# Project_OLIA.net
KiCad netlist of a schematic drawn in Altium Designer
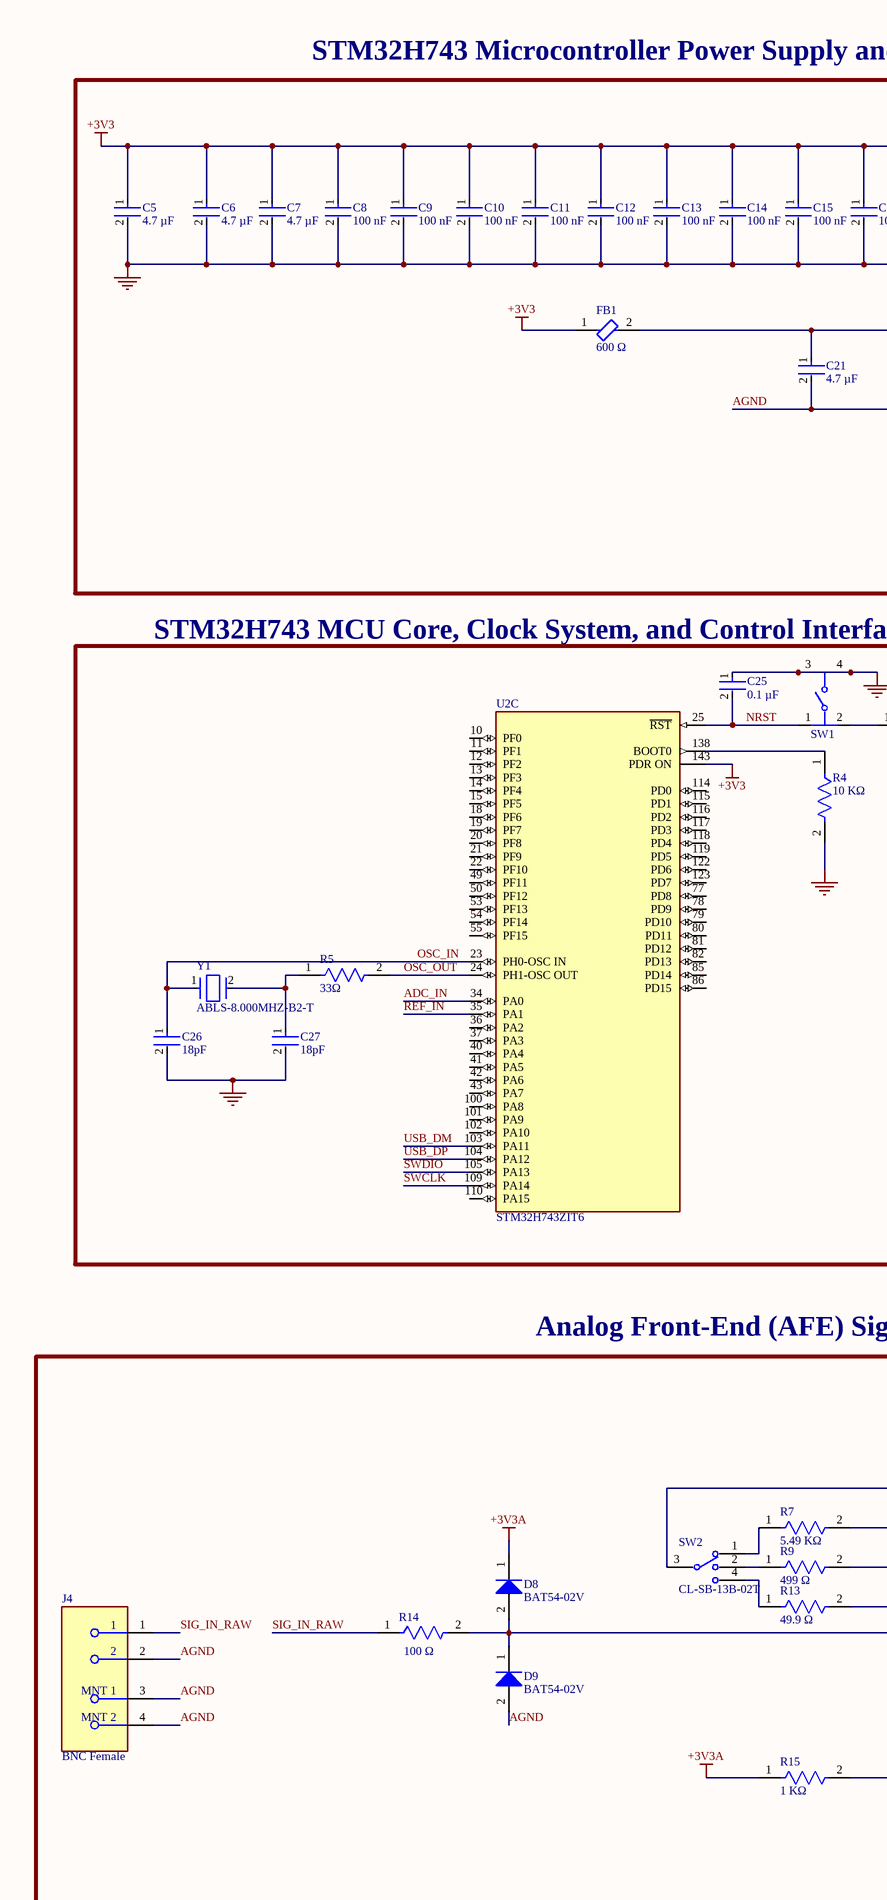
[diagram p0: Project_OLIA.SchDoc, left]
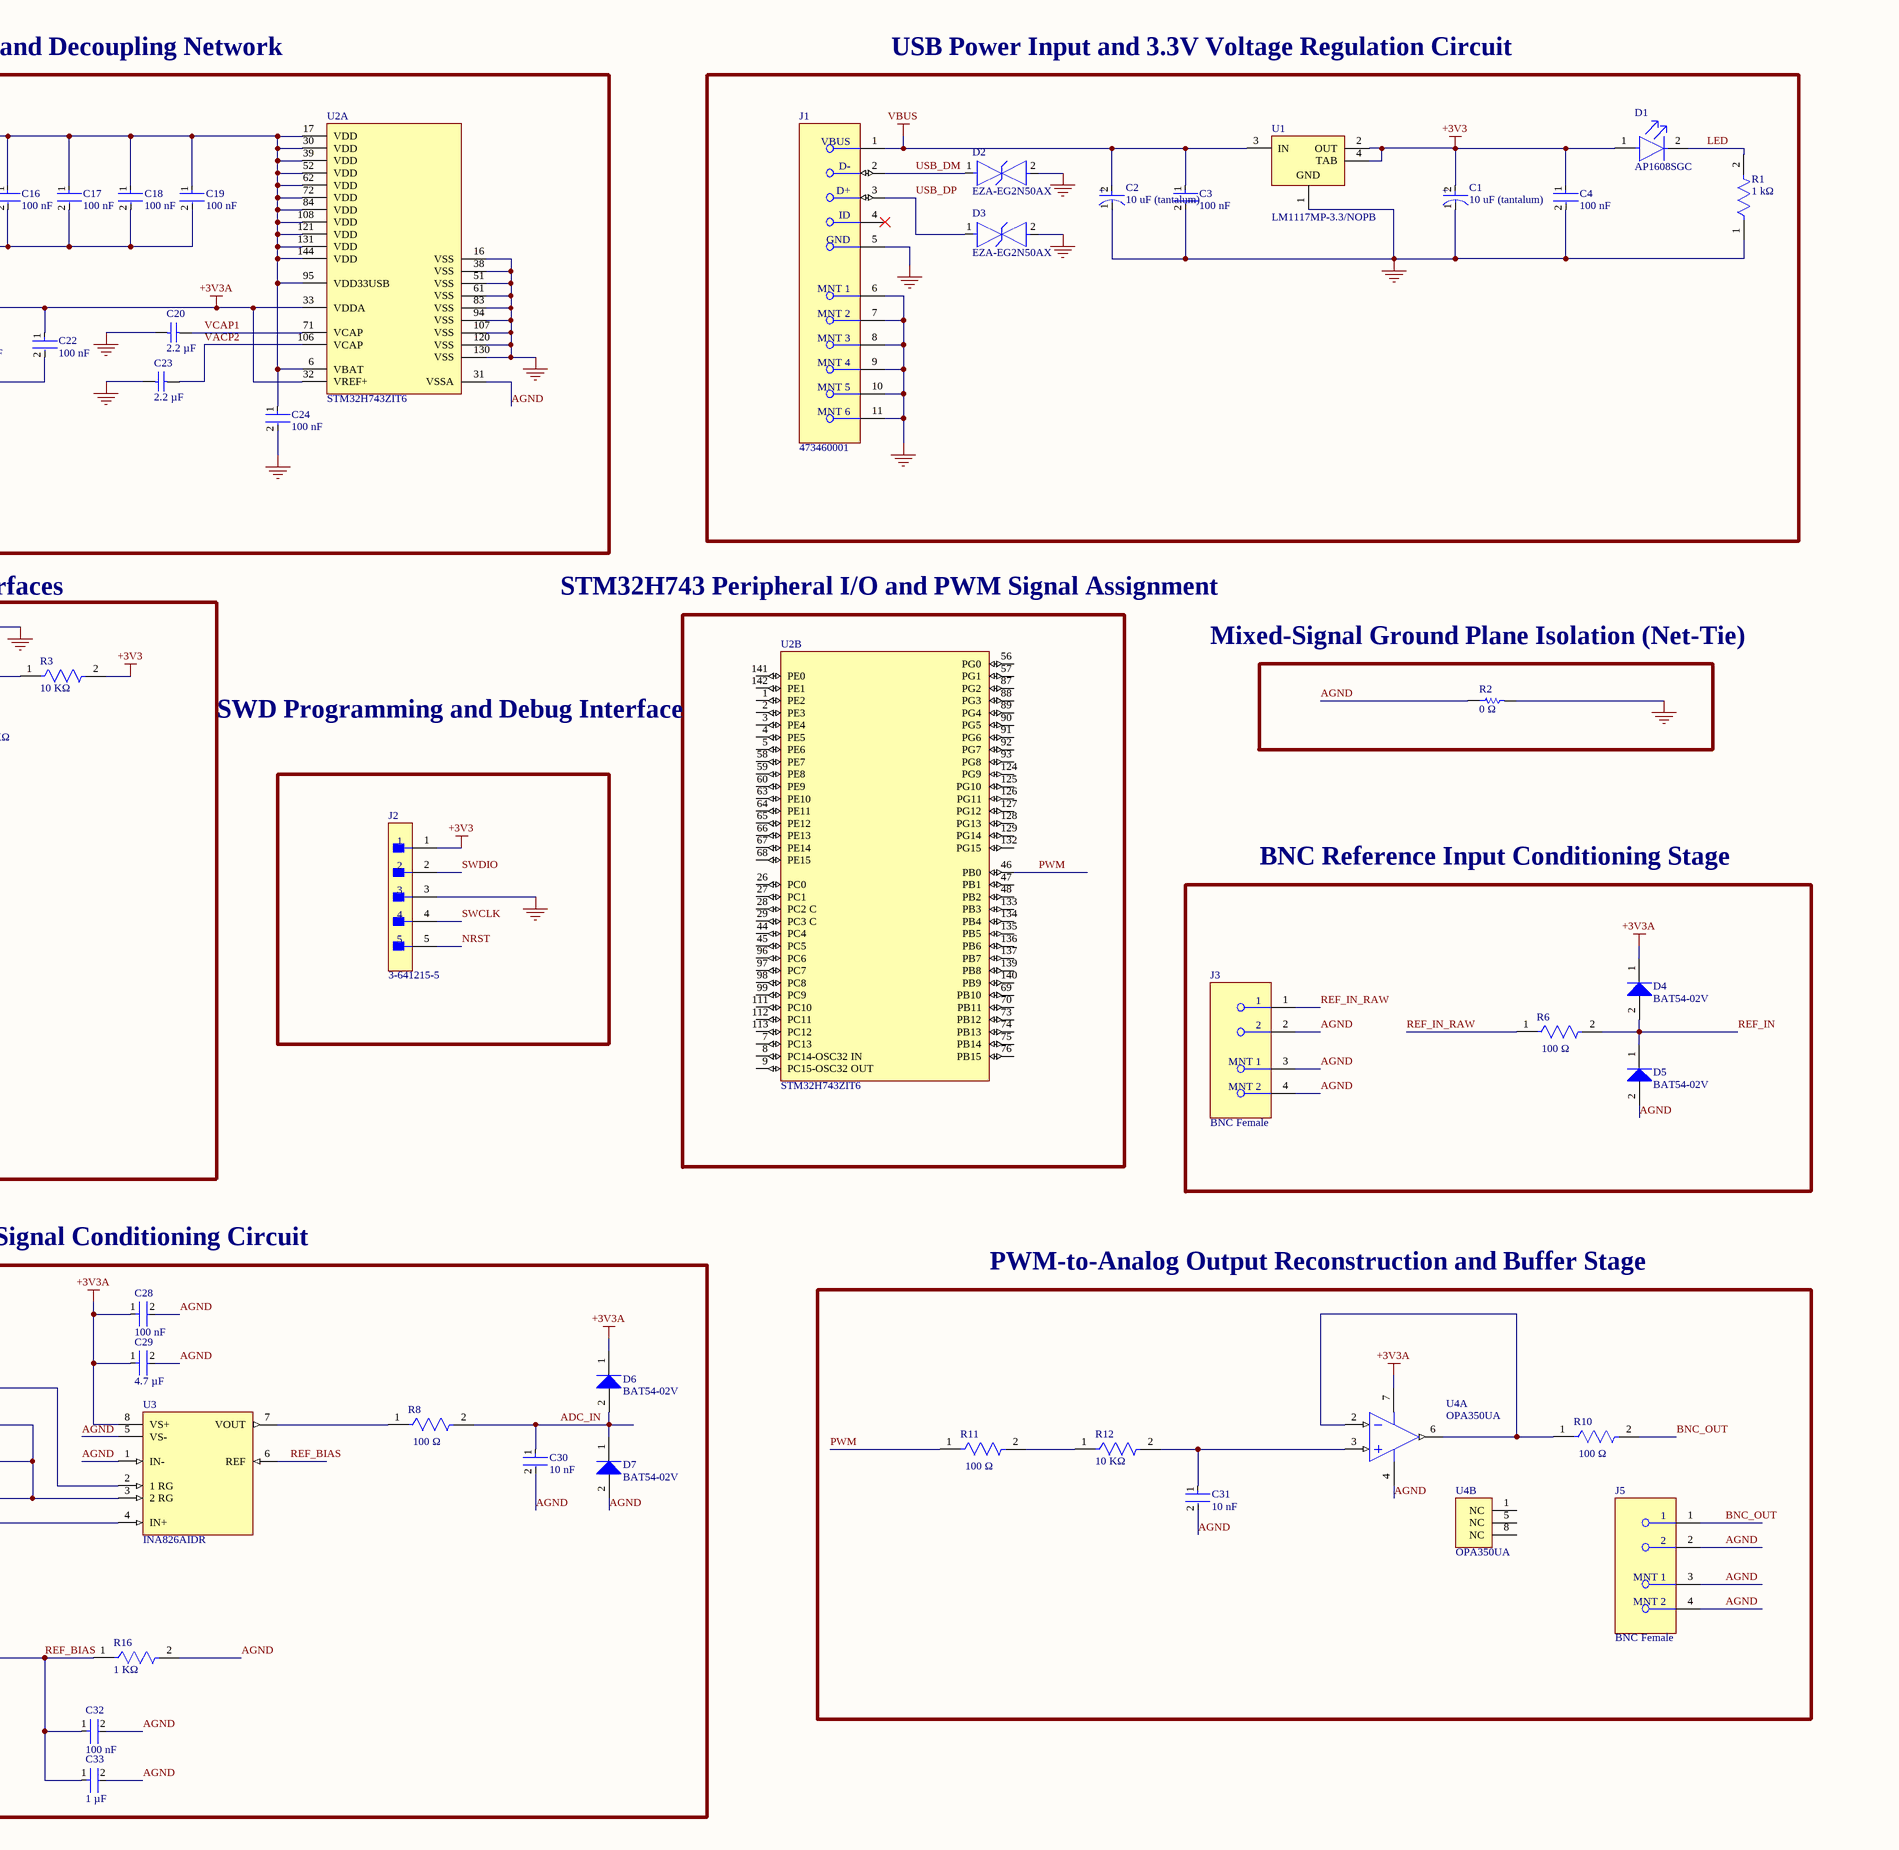
[diagram p1: Project_OLIA.SchDoc, right]

(export (version "E")
  (design (tool "Eeschema 10.0.6"))
  (components
    (comp (ref "C1")
      (value "10 uF (tantalum)")
      (footprint "FP-T491B106K016AT-MFG")
      (description "CAP TANT 10UF 10% 16V 1411")
      (fields (field (name "TOLERANCE") "10%") (field (name "VOLTAGE") "16V"))
      (libsource (lib "Altium Content Vault") (part "cf48714ba7e38822c1575c7ec0b6d1f"))
    )
    (comp (ref "C2")
      (value "10 uF (tantalum)")
      (footprint "FP-T491B106K016AT-MFG")
      (description "CAP TANT 10UF 10% 16V 1411")
      (fields (field (name "TOLERANCE") "10%") (field (name "VOLTAGE") "16V"))
      (libsource (lib "Altium Content Vault") (part "cf48714ba7e38822c1575c7ec0b6d1f"))
    )
    (comp (ref "C3")
      (value "100 nF")
      (footprint "FP-0603B104K500CT-IPC_C")
      (description "CAP CER 0.1UF 50V X7R 0603")
      (fields (field (name "TOLERANCE") "10%"))
      (libsource (lib "Altium Content Vault") (part "02cd4be3c70576c341d710602a673aa"))
    )
    (comp (ref "C4")
      (value "100 nF")
      (footprint "FP-0603B104K500CT-IPC_C")
      (description "CAP CER 0.1UF 50V X7R 0603")
      (fields (field (name "TOLERANCE") "10%"))
      (libsource (lib "Altium Content Vault") (part "02cd4be3c70576c341d710602a673aa"))
    )
    (comp (ref "C5")
      (value "4.7 µF")
      (footprint "FP-GCM31C-0_2-e0_3_0_8-IPC_A")
      (description "Ceramic Capacitor for Automotive 4.7uF ±10% 50VDC X7S 1206 Embossed T/R")
      (fields (field (name "TOLERANCE") "10%"))
      (libsource (lib "Altium Content Vault") (part "11868f565c42a9108669ba33697ecf6"))
    )
    (comp (ref "C6")
      (value "4.7 µF")
      (footprint "FP-GCM31C-0_2-e0_3_0_8-IPC_A")
      (description "Ceramic Capacitor for Automotive 4.7uF ±10% 50VDC X7S 1206 Embossed T/R")
      (fields (field (name "TOLERANCE") "10%"))
      (libsource (lib "Altium Content Vault") (part "11868f565c42a9108669ba33697ecf6"))
    )
    (comp (ref "C7")
      (value "4.7 µF")
      (footprint "FP-GCM31C-0_2-e0_3_0_8-IPC_A")
      (description "Ceramic Capacitor for Automotive 4.7uF ±10% 50VDC X7S 1206 Embossed T/R")
      (fields (field (name "TOLERANCE") "10%"))
      (libsource (lib "Altium Content Vault") (part "11868f565c42a9108669ba33697ecf6"))
    )
    (comp (ref "C8")
      (value "100 nF")
      (footprint "FP-0603B104K500CT-IPC_C")
      (description "CAP CER 0.1UF 50V X7R 0603")
      (fields (field (name "TOLERANCE") "10%"))
      (libsource (lib "Altium Content Vault") (part "02cd4be3c70576c341d710602a673aa"))
    )
    (comp (ref "C9")
      (value "100 nF")
      (footprint "FP-0603B104K500CT-IPC_C")
      (description "CAP CER 0.1UF 50V X7R 0603")
      (fields (field (name "TOLERANCE") "10%"))
      (libsource (lib "Altium Content Vault") (part "02cd4be3c70576c341d710602a673aa"))
    )
    (comp (ref "C10")
      (value "100 nF")
      (footprint "FP-0603B104K500CT-IPC_C")
      (description "CAP CER 0.1UF 50V X7R 0603")
      (fields (field (name "TOLERANCE") "10%"))
      (libsource (lib "Altium Content Vault") (part "02cd4be3c70576c341d710602a673aa"))
    )
    (comp (ref "C11")
      (value "100 nF")
      (footprint "FP-0603B104K500CT-IPC_C")
      (description "CAP CER 0.1UF 50V X7R 0603")
      (fields (field (name "TOLERANCE") "10%"))
      (libsource (lib "Altium Content Vault") (part "02cd4be3c70576c341d710602a673aa"))
    )
    (comp (ref "C12")
      (value "100 nF")
      (footprint "FP-0603B104K500CT-IPC_C")
      (description "CAP CER 0.1UF 50V X7R 0603")
      (fields (field (name "TOLERANCE") "10%"))
      (libsource (lib "Altium Content Vault") (part "02cd4be3c70576c341d710602a673aa"))
    )
    (comp (ref "C13")
      (value "100 nF")
      (footprint "FP-0603B104K500CT-IPC_C")
      (description "CAP CER 0.1UF 50V X7R 0603")
      (fields (field (name "TOLERANCE") "10%"))
      (libsource (lib "Altium Content Vault") (part "02cd4be3c70576c341d710602a673aa"))
    )
    (comp (ref "C14")
      (value "100 nF")
      (footprint "FP-0603B104K500CT-IPC_C")
      (description "CAP CER 0.1UF 50V X7R 0603")
      (fields (field (name "TOLERANCE") "10%"))
      (libsource (lib "Altium Content Vault") (part "02cd4be3c70576c341d710602a673aa"))
    )
    (comp (ref "C15")
      (value "100 nF")
      (footprint "FP-0603B104K500CT-IPC_C")
      (description "CAP CER 0.1UF 50V X7R 0603")
      (fields (field (name "TOLERANCE") "10%"))
      (libsource (lib "Altium Content Vault") (part "02cd4be3c70576c341d710602a673aa"))
    )
    (comp (ref "C16")
      (value "100 nF")
      (footprint "FP-0603B104K500CT-IPC_C")
      (description "CAP CER 0.1UF 50V X7R 0603")
      (fields (field (name "TOLERANCE") "10%"))
      (libsource (lib "Altium Content Vault") (part "02cd4be3c70576c341d710602a673aa"))
    )
    (comp (ref "C17")
      (value "100 nF")
      (footprint "FP-0603B104K500CT-IPC_C")
      (description "CAP CER 0.1UF 50V X7R 0603")
      (fields (field (name "TOLERANCE") "10%"))
      (libsource (lib "Altium Content Vault") (part "02cd4be3c70576c341d710602a673aa"))
    )
    (comp (ref "C18")
      (value "100 nF")
      (footprint "FP-0603B104K500CT-IPC_C")
      (description "CAP CER 0.1UF 50V X7R 0603")
      (fields (field (name "TOLERANCE") "10%"))
      (libsource (lib "Altium Content Vault") (part "02cd4be3c70576c341d710602a673aa"))
    )
    (comp (ref "C19")
      (value "100 nF")
      (footprint "FP-0603B104K500CT-IPC_C")
      (description "CAP CER 0.1UF 50V X7R 0603")
      (fields (field (name "TOLERANCE") "10%"))
      (libsource (lib "Altium Content Vault") (part "02cd4be3c70576c341d710602a673aa"))
    )
    (comp (ref "C20")
      (value "2.2 µF")
      (footprint "CAPC0603X33X15ML03T05")
      (fields
        (field (name "MANUFACTURER") "AVX Interconnect / Elco")
        (field (name "PART NUMBER") "0201ZD225MAT2A")
      )
      (libsource (lib "Altium Content Vault") (part "CAP"))
    )
    (comp (ref "C21")
      (value "4.7 µF")
      (footprint "FP-GCM31C-0_2-e0_3_0_8-IPC_A")
      (description "Ceramic Capacitor for Automotive 4.7uF ±10% 50VDC X7S 1206 Embossed T/R")
      (fields (field (name "TOLERANCE") "10%"))
      (libsource (lib "Altium Content Vault") (part "11868f565c42a9108669ba33697ecf6"))
    )
    (comp (ref "C22")
      (value "100 nF")
      (footprint "FP-0603B104K500CT-IPC_C")
      (description "CAP CER 0.1UF 50V X7R 0603")
      (fields (field (name "TOLERANCE") "10%"))
      (libsource (lib "Altium Content Vault") (part "02cd4be3c70576c341d710602a673aa"))
    )
    (comp (ref "C23")
      (value "2.2 µF")
      (footprint "CAPC0603X33X15ML03T05")
      (fields
        (field (name "MANUFACTURER") "AVX Interconnect / Elco")
        (field (name "PART NUMBER") "0201ZD225MAT2A")
      )
      (libsource (lib "Altium Content Vault") (part "CAP"))
    )
    (comp (ref "C24")
      (value "100 nF")
      (footprint "FP-0603B104K500CT-IPC_C")
      (description "CAP CER 0.1UF 50V X7R 0603")
      (fields (field (name "TOLERANCE") "10%"))
      (libsource (lib "Altium Content Vault") (part "02cd4be3c70576c341d710602a673aa"))
    )
    (comp (ref "C25")
      (value "0.1 µF")
      (footprint "FP-C0603C-CF-MFG")
      (description "CAP CER 0.1UF 50V X7R 0603")
      (fields (field (name "TOLERANCE") "0.1") (field (name "MANUFACTURER") "KEMET"))
      (libsource (lib "Altium Content Vault") (part "b4654b650e69147ec39a6b967a45e02"))
    )
    (comp (ref "C26")
      (value "18pF")
      (footprint "FP-GCM155-0_05-IPC_B")
      (description "Ceramic Capacitor for Automotive 18pF ±5% 50VDC C0G 0402 Paper T/R")
      (fields (field (name "TOLERANCE") "5%"))
      (libsource (lib "Altium Content Vault") (part "02cd4be3c70576c341d710602a673aa"))
    )
    (comp (ref "C27")
      (value "18pF")
      (footprint "FP-GCM155-0_05-IPC_B")
      (description "Ceramic Capacitor for Automotive 18pF ±5% 50VDC C0G 0402 Paper T/R")
      (fields (field (name "TOLERANCE") "5%"))
      (libsource (lib "Altium Content Vault") (part "02cd4be3c70576c341d710602a673aa"))
    )
    (comp (ref "C28")
      (value "100 nF")
      (footprint "FP-0603B104K500CT-IPC_C")
      (description "CAP CER 0.1UF 50V X7R 0603")
      (fields (field (name "TOLERANCE") "10%"))
      (libsource (lib "Altium Content Vault") (part "02cd4be3c70576c341d710602a673aa"))
    )
    (comp (ref "C29")
      (value "4.7 µF")
      (footprint "FP-GCM31C-0_2-e0_3_0_8-IPC_A")
      (description "Ceramic Capacitor for Automotive 4.7uF ±10% 50VDC X7S 1206 Embossed T/R")
      (fields (field (name "TOLERANCE") "10%"))
      (libsource (lib "Altium Content Vault") (part "11868f565c42a9108669ba33697ecf6"))
    )
    (comp (ref "C30")
      (value "10 nF")
      (footprint "FP-GCM155-0_05-IPC_C")
      (description "Ceramic Capacitor for Automotive 10nF ±10% 25VDC X7R 0402 Paper T/R")
      (fields (field (name "VOLTAGE") "25V") (field (name "TOLERANCE") "10%"))
      (libsource (lib "Altium Content Vault") (part "02cd4be3c70576c341d710602a673aa"))
    )
    (comp (ref "C31")
      (value "10 nF")
      (footprint "FP-GCM155-0_05-IPC_C")
      (description "Ceramic Capacitor for Automotive 10nF ±10% 25VDC X7R 0402 Paper T/R")
      (fields (field (name "VOLTAGE") "25V") (field (name "TOLERANCE") "10%"))
      (libsource (lib "Altium Content Vault") (part "02cd4be3c70576c341d710602a673aa"))
    )
    (comp (ref "C32")
      (value "100 nF")
      (footprint "FP-0603B104K500CT-IPC_C")
      (description "CAP CER 0.1UF 50V X7R 0603")
      (fields (field (name "TOLERANCE") "10%"))
      (libsource (lib "Altium Content Vault") (part "02cd4be3c70576c341d710602a673aa"))
    )
    (comp (ref "C33")
      (value "1 µF")
      (footprint "FP-GRM21B-0_2-e0_2_0_7-MFG")
      (description "Chip Multilayer Ceramic Capacitors for General Purpose, 0805, 1.0uF, X7S, 22%, 10%, 100V")
      (fields (field (name "TOLERANCE") "10%"))
      (libsource (lib "Altium Content Vault") (part "b4654b650e69147ec39a6b967a45e02"))
    )
    (comp (ref "D1")
      (value "AP1608SGC")
      (footprint "FP-AP1608SGC-MFG")
      (description "Standard LEDs - SMD GREEN WATER CLEAR")
      (libsource (lib "Altium Content Vault") (part "ab1c01a81903e929fc6c44469aada92"))
    )
    (comp (ref "D2")
      (value "EZA-EG2N50AX")
      (footprint "FP-EZAEG2N-MFG")
      (description "EZA-EG2N50AX Esd Suppressor, 50V, 0402 Rohs Compliant: Yes")
      (libsource (lib "Altium Content Vault") (part "EZA-EG2N50AX"))
    )
    (comp (ref "D3")
      (value "EZA-EG2N50AX")
      (footprint "FP-EZAEG2N-MFG")
      (description "EZA-EG2N50AX Esd Suppressor, 50V, 0402 Rohs Compliant: Yes")
      (libsource (lib "Altium Content Vault") (part "EZA-EG2N50AX"))
    )
    (comp (ref "D4")
      (value "BAT54-02V")
      (footprint "INF-SC79_V")
      (description "Silicon Schottky Diode, SC79, Reel, Green")
      (fields (field (name "MANUFACTURER") "Infineon"))
      (libsource (lib "Altium Content Vault") (part "INF-D_K1A2-2"))
    )
    (comp (ref "D5")
      (value "BAT54-02V")
      (footprint "INF-SC79_V")
      (description "Silicon Schottky Diode, SC79, Reel, Green")
      (fields (field (name "MANUFACTURER") "Infineon"))
      (libsource (lib "Altium Content Vault") (part "INF-D_K1A2-2"))
    )
    (comp (ref "D6")
      (value "BAT54-02V")
      (footprint "INF-SC79_V")
      (description "Silicon Schottky Diode, SC79, Reel, Green")
      (fields (field (name "MANUFACTURER") "Infineon"))
      (libsource (lib "Altium Content Vault") (part "INF-D_K1A2-2"))
    )
    (comp (ref "D7")
      (value "BAT54-02V")
      (footprint "INF-SC79_V")
      (description "Silicon Schottky Diode, SC79, Reel, Green")
      (fields (field (name "MANUFACTURER") "Infineon"))
      (libsource (lib "Altium Content Vault") (part "INF-D_K1A2-2"))
    )
    (comp (ref "D8")
      (value "BAT54-02V")
      (footprint "INF-SC79_V")
      (description "Silicon Schottky Diode, SC79, Reel, Green")
      (fields (field (name "MANUFACTURER") "Infineon"))
      (libsource (lib "Altium Content Vault") (part "INF-D_K1A2-2"))
    )
    (comp (ref "D9")
      (value "BAT54-02V")
      (footprint "INF-SC79_V")
      (description "Silicon Schottky Diode, SC79, Reel, Green")
      (fields (field (name "MANUFACTURER") "Infineon"))
      (libsource (lib "Altium Content Vault") (part "INF-D_K1A2-2"))
    )
    (comp (ref "FB1")
      (value "600 Ω")
      (footprint "FP-MMZ1608-0_6-MFG")
      (description "Signal Line Ferrite Bead 600 Ω 100MHz 500mA DCR 400mΩ AEC-Q200 SMD 0603")
      (fields (field (name "TOLERANCE") "25%"))
      (libsource (lib "Altium Content Vault") (part "5f30dd21d616792df468990f7003faa"))
    )
    (comp (ref "J1")
      (value "473460001")
      (footprint "FP-473460001-MFG")
      (description "CONN RCPT USB2.0 MICRO B SMD R/A")
      (fields
        (field (name "OCTOPART") "https://octopart.com/47346-0001-molex-7164928")
        (field (name "MANUFACTURER") "Molex")
      )
      (libsource (lib "Altium Content Vault") (part "53ae1f1d9b557310b43ca686e5bb76a"))
    )
    (comp (ref "J2")
      (value "3-641215-5")
      (footprint "FP-3-641215-5-MFG")
      (description "CONN HEADER VERT 5POS 2.54MM")
      (fields
        (field (name "MANUFACTURER") "TE Connectivity")
        (field (name "OCTOPART") "https://octopart.com/3-641215-5-te+connectivity-40938285")
      )
      (libsource (lib "Altium Content Vault") (part "bf93c07fd2649a848d0ec8585582aab"))
    )
    (comp (ref "J3")
      (value "BNC Female")
      (footprint "FP-73137-5003-MFG")
      (description "73137-5003 Connector BNC Female 0Hz To 2GHz 50 Ohm Solder Right Angle Through Hole Gold Tray")
      (libsource (lib "Altium Content Vault") (part "3abcdd43b2a612663cc81d8cccb07ec"))
    )
    (comp (ref "J4")
      (value "BNC Female")
      (footprint "FP-73137-5003-MFG")
      (description "73137-5003 Connector BNC Female 0Hz To 2GHz 50 Ohm Solder Right Angle Through Hole Gold Tray")
      (libsource (lib "Altium Content Vault") (part "3abcdd43b2a612663cc81d8cccb07ec"))
    )
    (comp (ref "J5")
      (value "BNC Female")
      (footprint "FP-73137-5003-MFG")
      (description "73137-5003 Connector BNC Female 0Hz To 2GHz 50 Ohm Solder Right Angle Through Hole Gold Tray")
      (libsource (lib "Altium Content Vault") (part "3abcdd43b2a612663cc81d8cccb07ec"))
    )
    (comp (ref "R1")
      (value "1 kΩ")
      (footprint "FP-RMCF0603-MFG")
      (description "1kΩ ±1% 0.1W 0603 Thick Film Chip Resistor AEC-Q200 compliant")
      (fields (field (name "TOLERANCE") "1%"))
      (libsource (lib "Altium Content Vault") (part "1029c3af85768c4190bb7ad29bc67b5"))
    )
    (comp (ref "R2")
      (value "0 Ω")
      (footprint "RESC1609X50X30LL10T20")
      (fields (field (name "MANUFACTURER") "Vishay Dale") (field (name "PART NUMBER") "CRCW06030000Z0EC"))
      (libsource (lib "Altium Content Vault") (part "RES"))
    )
    (comp (ref "R3")
      (value "10 KΩ")
      (footprint "FP-RC1005-IPC_B")
      (description "Res Thick Film 0402 10kΩ 1% 0.063W ±100ppm/°C Molded SMD T/R")
      (fields (field (name "TOLERANCE") "1%"))
      (libsource (lib "Altium Content Vault") (part "1029c3af85768c4190bb7ad29bc67b5"))
    )
    (comp (ref "R4")
      (value "10 KΩ")
      (footprint "FP-RC1005-IPC_B")
      (description "Res Thick Film 0402 10kΩ 1% 0.063W ±100ppm/°C Molded SMD T/R")
      (fields (field (name "TOLERANCE") "1%"))
      (libsource (lib "Altium Content Vault") (part "1029c3af85768c4190bb7ad29bc67b5"))
    )
    (comp (ref "R5")
      (value "33Ω")
      (footprint "FP-CRCW2512-e3-IPC_C")
      (description "RES Thick Film, 33Ω, 5%, 1W, 200ppm/°C, 2512")
      (fields (field (name "TOLERANCE") "5%"))
      (libsource (lib "Altium Content Vault") (part "1029c3af85768c4190bb7ad29bc67b5"))
    )
    (comp (ref "R6")
      (value "100 Ω")
      (footprint "FP-ERA1A-IPC_B")
      (description "RES SMD 100 OHM 0.1% 1/20W 0201")
      (fields (field (name "TOLERANCE") "0.1%"))
      (libsource (lib "Altium Content Vault") (part "1029c3af85768c4190bb7ad29bc67b5"))
    )
    (comp (ref "R7")
      (value "5.49 KΩ")
      (footprint "FP-CRCW0805-e3-IPC_B")
      (description "RES Thick Film, 5.49kΩ, 1%, 0.125W, 100ppm/°C, 0805")
      (fields (field (name "TOLERANCE") "1%"))
      (libsource (lib "Altium Content Vault") (part "1029c3af85768c4190bb7ad29bc67b5"))
    )
    (comp (ref "R8")
      (value "100 Ω")
      (footprint "FP-ERA1A-IPC_B")
      (description "RES SMD 100 OHM 0.1% 1/20W 0201")
      (fields (field (name "TOLERANCE") "0.1%"))
      (libsource (lib "Altium Content Vault") (part "1029c3af85768c4190bb7ad29bc67b5"))
    )
    (comp (ref "R9")
      (value "499 Ω")
      (footprint "FP-CRCW0603-e3-MFG")
      (description "RES Thick Film, 499Ω, 1%, 0.1W, 100ppm/°C, 0603")
      (fields (field (name "TOLERANCE") "1%"))
      (libsource (lib "Altium Content Vault") (part "1029c3af85768c4190bb7ad29bc67b5"))
    )
    (comp (ref "R10")
      (value "100 Ω")
      (footprint "FP-ERA1A-IPC_B")
      (description "RES SMD 100 OHM 0.1% 1/20W 0201")
      (fields (field (name "TOLERANCE") "0.1%"))
      (libsource (lib "Altium Content Vault") (part "1029c3af85768c4190bb7ad29bc67b5"))
    )
    (comp (ref "R11")
      (value "100 Ω")
      (footprint "FP-ERA1A-IPC_B")
      (description "RES SMD 100 OHM 0.1% 1/20W 0201")
      (fields (field (name "TOLERANCE") "0.1%"))
      (libsource (lib "Altium Content Vault") (part "1029c3af85768c4190bb7ad29bc67b5"))
    )
    (comp (ref "R12")
      (value "10 KΩ")
      (footprint "FP-RC1005-IPC_B")
      (description "Res Thick Film 0402 10kΩ 1% 0.063W ±100ppm/°C Molded SMD T/R")
      (fields (field (name "TOLERANCE") "1%"))
      (libsource (lib "Altium Content Vault") (part "1029c3af85768c4190bb7ad29bc67b5"))
    )
    (comp (ref "R13")
      (value "49.9 Ω")
      (footprint "FP-AC2512-MFG")
      (description "RES SMD 49.9 OHM 1% 1W 2512")
      (fields
        (field (name "MANUFACTURER") "Yageo")
        (field (name "OCTOPART") "https://octopart.com/ac2512fk-0749r9l-yageo-71370116")
      )
      (libsource (lib "Altium Content Vault") (part "1029c3af85768c4190bb7ad29bc67b5"))
    )
    (comp (ref "R14")
      (value "100 Ω")
      (footprint "FP-ERA1A-IPC_B")
      (description "RES SMD 100 OHM 0.1% 1/20W 0201")
      (fields (field (name "TOLERANCE") "0.1%"))
      (libsource (lib "Altium Content Vault") (part "1029c3af85768c4190bb7ad29bc67b5"))
    )
    (comp (ref "R15")
      (value "1 KΩ")
      (footprint "FP-RP732B-MFG")
      (description "Res Thin Film 1206 1.0KΩ 0.1% 0.25W 15ppm/°C Molded SMD")
      (fields
        (field (name "TOLERANCE") "0.1%")
        (field (name "OCTOPART") "https://octopart.com/rp73d2b1k0btdf-te+connectivity-22741139")
      )
      (libsource (lib "Altium Content Vault") (part "1029c3af85768c4190bb7ad29bc67b5"))
    )
    (comp (ref "R16")
      (value "1 KΩ")
      (footprint "FP-RP732B-MFG")
      (description "Res Thin Film 1206 1.0KΩ 0.1% 0.25W 15ppm/°C Molded SMD")
      (fields
        (field (name "TOLERANCE") "0.1%")
        (field (name "OCTOPART") "https://octopart.com/rp73d2b1k0btdf-te+connectivity-22741139")
      )
      (libsource (lib "Altium Content Vault") (part "1029c3af85768c4190bb7ad29bc67b5"))
    )
    (comp (ref "SW1")
      (value "1-1977223-9")
      (footprint "FP-1-1977223-9-MFG")
      (description "SWITCH TACTILE SPST-NO 0.05A 24V")
      (libsource (lib "Altium Content Vault") (part "b8895f3f4cefb76e1819d2863dba89b"))
    )
    (comp (ref "SW2")
      (value "CL-SB-13B-02T")
      (footprint "FP-CL-SB-13B-02T-MFG")
      (description "CL-SB-13B-02T Switch Slide ON-ON-ON SP3T Top 200mA 12VDC 10000Cycles Gullwing T/R")
      (libsource (lib "Altium Content Vault") (part "5552a05cdd07c74f2f3fb1217988f51"))
    )
    (comp (ref "U1")
      (value "LM1117MP-3.3/NOPB")
      (footprint "DCY0004A_L")
      (description "800mA Low-Dropout Linear Regulator, 4-pin SOT-223, Pb-Free")
      (fields (field (name "MANUFACTURER") "Texas Instruments"))
      (libsource (lib "Altium Content Vault") (part "PM-REG-LM1086-SOT4"))
    )
    (comp (ref "U2")
      (value "STM32H743ZIT6")
      (footprint "FP-LQFP144-1A-MFG")
      (description "IC MCU 32BIT 2MB FLASH 144LQFP")
      (fields
        (field (name "MANUFACTURER") "STMicroelectronics")
        (field (name "OCTOPART") "https://octopart.com/stm32h743zit6-stmicroelectronics-76372529")
      )
      (libsource (lib "Altium Content Vault") (part "4977c5c7f8d170b58ef15f889e64ba1"))
    )
    (comp (ref "U3")
      (value "INA826AIDR")
      (footprint "FP-D0008A-IPC_A")
      (description "IC INST AMP 1 CIRCUIT 8SOIC")
      (libsource (lib "Altium Content Vault") (part "037b479d141f114d33bcf3e617bad63"))
    )
    (comp (ref "U4")
      (value "OPA350UA")
      (footprint "D0008A_M")
      (fields (field (name "MANUFACTURER") "Texas Instruments"))
      (libsource (lib "Altium Content Vault") (part "TI-OPA-8_1"))
    )
    (comp (ref "Y1")
      (value "ABLS-8.000MHZ-B2-T")
      (footprint "FP-ABLS-MFG")
      (description "CRYSTAL 8.0000MHZ 18PF SMD")
      (fields (field (name "TOLERANCE") "20ppm"))
      (libsource (lib "Altium Content Vault") (part "c23a69dc6c9e2f18f2079038eb95dd1"))
    )
  )
  (nets
    (net (code "1") (name "+3V3") (class "Default")
      (node (ref "C1") (pin "2") (pinfunction "A_2") (pintype "passive"))
      (node (ref "C10") (pin "1") (pinfunction "1_1") (pintype "passive"))
      (node (ref "C11") (pin "1") (pinfunction "1_1") (pintype "passive"))
      (node (ref "C12") (pin "1") (pinfunction "1_1") (pintype "passive"))
      (node (ref "C13") (pin "1") (pinfunction "1_1") (pintype "passive"))
      (node (ref "C14") (pin "1") (pinfunction "1_1") (pintype "passive"))
      (node (ref "C15") (pin "1") (pinfunction "1_1") (pintype "passive"))
      (node (ref "C16") (pin "1") (pinfunction "1_1") (pintype "passive"))
      (node (ref "C17") (pin "1") (pinfunction "1_1") (pintype "passive"))
      (node (ref "C18") (pin "1") (pinfunction "1_1") (pintype "passive"))
      (node (ref "C19") (pin "1") (pinfunction "1_1") (pintype "passive"))
      (node (ref "C24") (pin "1") (pinfunction "1_1") (pintype "passive"))
      (node (ref "C4") (pin "1") (pinfunction "1_1") (pintype "passive"))
      (node (ref "C5") (pin "1") (pinfunction "1_1") (pintype "passive"))
      (node (ref "C6") (pin "1") (pinfunction "1_1") (pintype "passive"))
      (node (ref "C7") (pin "1") (pinfunction "1_1") (pintype "passive"))
      (node (ref "C8") (pin "1") (pinfunction "1_1") (pintype "passive"))
      (node (ref "C9") (pin "1") (pinfunction "1_1") (pintype "passive"))
      (node (ref "D1") (pin "1") (pinfunction "A_1") (pintype "passive"))
      (node (ref "FB1") (pin "1") (pinfunction "1_1") (pintype "passive"))
      (node (ref "J2") (pin "1") (pinfunction "1_1") (pintype "passive"))
      (node (ref "R3") (pin "2") (pinfunction "2_2") (pintype "passive"))
      (node (ref "U1") (pin "2") (pinfunction "OUT_2") (pintype "power_in"))
      (node (ref "U1") (pin "4") (pinfunction "TAB_4") (pintype "power_in"))
      (node (ref "U2") (pin "108") (pinfunction "VDD_108") (pintype "power_in"))
      (node (ref "U2") (pin "121") (pinfunction "VDD_121") (pintype "power_in"))
      (node (ref "U2") (pin "131") (pinfunction "VDD_131") (pintype "power_in"))
      (node (ref "U2") (pin "143") (pinfunction "PDR_ON_143") (pintype "power_in"))
      (node (ref "U2") (pin "144") (pinfunction "VDD_144") (pintype "power_in"))
      (node (ref "U2") (pin "17") (pinfunction "VDD_17") (pintype "power_in"))
      (node (ref "U2") (pin "30") (pinfunction "VDD_30") (pintype "power_in"))
      (node (ref "U2") (pin "39") (pinfunction "VDD_39") (pintype "power_in"))
      (node (ref "U2") (pin "52") (pinfunction "VDD_52") (pintype "power_in"))
      (node (ref "U2") (pin "6") (pinfunction "VBAT_6") (pintype "power_in"))
      (node (ref "U2") (pin "62") (pinfunction "VDD_62") (pintype "power_in"))
      (node (ref "U2") (pin "72") (pinfunction "VDD_72") (pintype "power_in"))
      (node (ref "U2") (pin "84") (pinfunction "VDD_84") (pintype "power_in"))
      (node (ref "U2") (pin "95") (pinfunction "VDD33USB_95") (pintype "power_in"))
    )
    (net (code "2") (name "+3V3A") (class "Default")
      (node (ref "C21") (pin "1") (pinfunction "1_1") (pintype "passive"))
      (node (ref "C22") (pin "1") (pinfunction "1_1") (pintype "passive"))
      (node (ref "C28") (pin "1") (pinfunction "1_1") (pintype "passive"))
      (node (ref "C29") (pin "1") (pinfunction "1_1") (pintype "passive"))
      (node (ref "D4") (pin "1") (pinfunction "K_1") (pintype "passive"))
      (node (ref "D6") (pin "1") (pinfunction "K_1") (pintype "passive"))
      (node (ref "D8") (pin "1") (pinfunction "K_1") (pintype "passive"))
      (node (ref "FB1") (pin "2") (pinfunction "2_2") (pintype "passive"))
      (node (ref "R15") (pin "1") (pinfunction "1_1") (pintype "passive"))
      (node (ref "U2") (pin "32") (pinfunction "VREF+_32") (pintype "power_in"))
      (node (ref "U2") (pin "33") (pinfunction "VDDA_33") (pintype "power_in"))
      (node (ref "U3") (pin "8") (pinfunction "VS+_8") (pintype "power_in"))
      (node (ref "U4") (pin "7") (pinfunction "V+_7") (pintype "power_in"))
    )
    (net (code "3") (name "/ADC_IN") (class "Default")
      (node (ref "C30") (pin "1") (pinfunction "1_1") (pintype "passive"))
      (node (ref "D6") (pin "2") (pinfunction "A_2") (pintype "passive"))
      (node (ref "D7") (pin "1") (pinfunction "K_1") (pintype "passive"))
      (node (ref "R8") (pin "2") (pinfunction "2_2") (pintype "passive"))
      (node (ref "U2") (pin "34") (pinfunction "PA0_34") (pintype "bidirectional"))
    )
    (net (code "4") (name "/AGND") (class "Default")
      (node (ref "C21") (pin "2") (pinfunction "2_2") (pintype "passive"))
      (node (ref "C22") (pin "2") (pinfunction "2_2") (pintype "passive"))
      (node (ref "C28") (pin "2") (pinfunction "2_2") (pintype "passive"))
      (node (ref "C29") (pin "2") (pinfunction "2_2") (pintype "passive"))
      (node (ref "C30") (pin "2") (pinfunction "2_2") (pintype "passive"))
      (node (ref "C31") (pin "2") (pinfunction "2_2") (pintype "passive"))
      (node (ref "C32") (pin "2") (pinfunction "2_2") (pintype "passive"))
      (node (ref "C33") (pin "2") (pinfunction "2_2") (pintype "passive"))
      (node (ref "D5") (pin "2") (pinfunction "A_2") (pintype "passive"))
      (node (ref "D7") (pin "2") (pinfunction "A_2") (pintype "passive"))
      (node (ref "D9") (pin "2") (pinfunction "A_2") (pintype "passive"))
      (node (ref "J3") (pin "2") (pinfunction "2_2") (pintype "passive"))
      (node (ref "J3") (pin "3") (pinfunction "MNT_1_3") (pintype "passive"))
      (node (ref "J3") (pin "4") (pinfunction "MNT_2_4") (pintype "passive"))
      (node (ref "J4") (pin "2") (pinfunction "2_2") (pintype "passive"))
      (node (ref "J4") (pin "3") (pinfunction "MNT_1_3") (pintype "passive"))
      (node (ref "J4") (pin "4") (pinfunction "MNT_2_4") (pintype "passive"))
      (node (ref "J5") (pin "2") (pinfunction "2_2") (pintype "passive"))
      (node (ref "J5") (pin "3") (pinfunction "MNT_1_3") (pintype "passive"))
      (node (ref "J5") (pin "4") (pinfunction "MNT_2_4") (pintype "passive"))
      (node (ref "R16") (pin "2") (pinfunction "2_2") (pintype "passive"))
      (node (ref "R2") (pin "1") (pinfunction "1_1") (pintype "passive"))
      (node (ref "U2") (pin "31") (pinfunction "VSSA_31") (pintype "power_in"))
      (node (ref "U3") (pin "1") (pinfunction "IN-_1") (pintype "input"))
      (node (ref "U3") (pin "5") (pinfunction "VS-_5") (pintype "power_in"))
      (node (ref "U4") (pin "4") (pinfunction "V-_4") (pintype "power_in"))
    )
    (net (code "5") (name "/BNC_OUT") (class "Default")
      (node (ref "J5") (pin "1") (pinfunction "1_1") (pintype "passive"))
      (node (ref "R10") (pin "2") (pinfunction "2_2") (pintype "passive"))
    )
    (net (code "6") (name "/LED") (class "Default")
      (node (ref "D1") (pin "2") (pinfunction "C_2") (pintype "passive"))
      (node (ref "R1") (pin "2") (pinfunction "2_2") (pintype "passive"))
    )
    (net (code "7") (name "/NRST") (class "Default")
      (node (ref "C25") (pin "2") (pinfunction "2_2") (pintype "passive"))
      (node (ref "J2") (pin "5") (pinfunction "5_5") (pintype "passive"))
      (node (ref "SW1") (pin "1") (pinfunction "1_1") (pintype "passive"))
      (node (ref "U2") (pin "25") (pinfunction "~{RST}_25") (pintype "input"))
    )
    (net (code "8") (name "/OSC_IN") (class "Default")
      (node (ref "C26") (pin "1") (pinfunction "1_1") (pintype "passive"))
      (node (ref "U2") (pin "23") (pinfunction "PH0-OSC_IN_23") (pintype "bidirectional"))
      (node (ref "Y1") (pin "1") (pinfunction "1_1") (pintype "passive"))
    )
    (net (code "9") (name "/OSC_OUT") (class "Default")
      (node (ref "R5") (pin "2") (pinfunction "2_2") (pintype "passive"))
      (node (ref "U2") (pin "24") (pinfunction "PH1-OSC_OUT_24") (pintype "bidirectional"))
    )
    (net (code "10") (name "/PWM") (class "Default")
      (node (ref "R11") (pin "1") (pinfunction "1_1") (pintype "passive"))
      (node (ref "U2") (pin "46") (pinfunction "PB0_46") (pintype "bidirectional"))
    )
    (net (code "11") (name "/REF_BIAS") (class "Default")
      (node (ref "C32") (pin "1") (pinfunction "1_1") (pintype "passive"))
      (node (ref "C33") (pin "1") (pinfunction "1_1") (pintype "passive"))
      (node (ref "R15") (pin "2") (pinfunction "2_2") (pintype "passive"))
      (node (ref "R16") (pin "1") (pinfunction "1_1") (pintype "passive"))
      (node (ref "U3") (pin "6") (pinfunction "REF_6") (pintype "input"))
    )
    (net (code "12") (name "/REF_IN") (class "Default")
      (node (ref "D4") (pin "2") (pinfunction "A_2") (pintype "passive"))
      (node (ref "D5") (pin "1") (pinfunction "K_1") (pintype "passive"))
      (node (ref "R6") (pin "2") (pinfunction "2_2") (pintype "passive"))
      (node (ref "U2") (pin "35") (pinfunction "PA1_35") (pintype "bidirectional"))
    )
    (net (code "13") (name "/REF_IN_RAW") (class "Default")
      (node (ref "J3") (pin "1") (pinfunction "1_1") (pintype "passive"))
      (node (ref "R6") (pin "1") (pinfunction "1_1") (pintype "passive"))
    )
    (net (code "14") (name "/SIG_IN_RAW") (class "Default")
      (node (ref "J4") (pin "1") (pinfunction "1_1") (pintype "passive"))
      (node (ref "R14") (pin "1") (pinfunction "1_1") (pintype "passive"))
    )
    (net (code "15") (name "/SWCLK") (class "Default")
      (node (ref "J2") (pin "4") (pinfunction "4_4") (pintype "passive"))
      (node (ref "U2") (pin "109") (pinfunction "PA14_109") (pintype "bidirectional"))
    )
    (net (code "16") (name "/SWDIO") (class "Default")
      (node (ref "J2") (pin "2") (pinfunction "2_2") (pintype "passive"))
      (node (ref "U2") (pin "105") (pinfunction "PA13_105") (pintype "bidirectional"))
    )
    (net (code "17") (name "/USB_DM") (class "Default")
      (node (ref "D2") (pin "1") (pinfunction "1_1") (pintype "passive"))
      (node (ref "J1") (pin "2") (pinfunction "D-_2") (pintype "bidirectional"))
      (node (ref "U2") (pin "103") (pinfunction "PA11_103") (pintype "bidirectional"))
    )
    (net (code "18") (name "/USB_DP") (class "Default")
      (node (ref "D3") (pin "1") (pinfunction "1_1") (pintype "passive"))
      (node (ref "J1") (pin "3") (pinfunction "D+_3") (pintype "bidirectional"))
      (node (ref "U2") (pin "104") (pinfunction "PA12_104") (pintype "bidirectional"))
    )
    (net (code "19") (name "/VACP2") (class "Default")
      (node (ref "C23") (pin "2") (pinfunction "2_2") (pintype "passive"))
      (node (ref "U2") (pin "106") (pinfunction "VCAP_106") (pintype "power_in"))
    )
    (net (code "20") (name "/VCAP1") (class "Default")
      (node (ref "C20") (pin "1") (pinfunction "1_1") (pintype "passive"))
      (node (ref "U2") (pin "71") (pinfunction "VCAP_71") (pintype "power_in"))
    )
    (net (code "21") (name "GND") (class "Default")
      (node (ref "C1") (pin "1") (pinfunction "C_1") (pintype "passive"))
      (node (ref "C10") (pin "2") (pinfunction "2_2") (pintype "passive"))
      (node (ref "C11") (pin "2") (pinfunction "2_2") (pintype "passive"))
      (node (ref "C12") (pin "2") (pinfunction "2_2") (pintype "passive"))
      (node (ref "C13") (pin "2") (pinfunction "2_2") (pintype "passive"))
      (node (ref "C14") (pin "2") (pinfunction "2_2") (pintype "passive"))
      (node (ref "C15") (pin "2") (pinfunction "2_2") (pintype "passive"))
      (node (ref "C16") (pin "2") (pinfunction "2_2") (pintype "passive"))
      (node (ref "C17") (pin "2") (pinfunction "2_2") (pintype "passive"))
      (node (ref "C18") (pin "2") (pinfunction "2_2") (pintype "passive"))
      (node (ref "C19") (pin "2") (pinfunction "2_2") (pintype "passive"))
      (node (ref "C2") (pin "1") (pinfunction "C_1") (pintype "passive"))
      (node (ref "C20") (pin "2") (pinfunction "2_2") (pintype "passive"))
      (node (ref "C23") (pin "1") (pinfunction "1_1") (pintype "passive"))
      (node (ref "C24") (pin "2") (pinfunction "2_2") (pintype "passive"))
      (node (ref "C25") (pin "1") (pinfunction "1_1") (pintype "passive"))
      (node (ref "C26") (pin "2") (pinfunction "2_2") (pintype "passive"))
      (node (ref "C27") (pin "2") (pinfunction "2_2") (pintype "passive"))
      (node (ref "C3") (pin "2") (pinfunction "2_2") (pintype "passive"))
      (node (ref "C4") (pin "2") (pinfunction "2_2") (pintype "passive"))
      (node (ref "C5") (pin "2") (pinfunction "2_2") (pintype "passive"))
      (node (ref "C6") (pin "2") (pinfunction "2_2") (pintype "passive"))
      (node (ref "C7") (pin "2") (pinfunction "2_2") (pintype "passive"))
      (node (ref "C8") (pin "2") (pinfunction "2_2") (pintype "passive"))
      (node (ref "C9") (pin "2") (pinfunction "2_2") (pintype "passive"))
      (node (ref "D2") (pin "2") (pinfunction "2_2") (pintype "passive"))
      (node (ref "D3") (pin "2") (pinfunction "2_2") (pintype "passive"))
      (node (ref "J1") (pin "10") (pinfunction "MNT_5_10") (pintype "passive"))
      (node (ref "J1") (pin "11") (pinfunction "MNT_6_11") (pintype "passive"))
      (node (ref "J1") (pin "5") (pinfunction "GND_5") (pintype "power_in"))
      (node (ref "J1") (pin "6") (pinfunction "MNT_1_6") (pintype "passive"))
      (node (ref "J1") (pin "7") (pinfunction "MNT_2_7") (pintype "passive"))
      (node (ref "J1") (pin "8") (pinfunction "MNT_3_8") (pintype "passive"))
      (node (ref "J1") (pin "9") (pinfunction "MNT_4_9") (pintype "passive"))
      (node (ref "J2") (pin "3") (pinfunction "3_3") (pintype "passive"))
      (node (ref "R1") (pin "1") (pinfunction "1_1") (pintype "passive"))
      (node (ref "R2") (pin "2") (pinfunction "2_2") (pintype "passive"))
      (node (ref "R4") (pin "2") (pinfunction "2_2") (pintype "passive"))
      (node (ref "SW1") (pin "3") (pinfunction "3_3") (pintype "passive"))
      (node (ref "SW1") (pin "4") (pinfunction "4_4") (pintype "passive"))
      (node (ref "U1") (pin "1") (pinfunction "GND_1") (pintype "power_in"))
      (node (ref "U2") (pin "107") (pinfunction "VSS_107") (pintype "power_in"))
      (node (ref "U2") (pin "120") (pinfunction "VSS_120") (pintype "power_in"))
      (node (ref "U2") (pin "130") (pinfunction "VSS_130") (pintype "power_in"))
      (node (ref "U2") (pin "16") (pinfunction "VSS_16") (pintype "power_in"))
      (node (ref "U2") (pin "38") (pinfunction "VSS_38") (pintype "power_in"))
      (node (ref "U2") (pin "51") (pinfunction "VSS_51") (pintype "power_in"))
      (node (ref "U2") (pin "61") (pinfunction "VSS_61") (pintype "power_in"))
      (node (ref "U2") (pin "83") (pinfunction "VSS_83") (pintype "power_in"))
      (node (ref "U2") (pin "94") (pinfunction "VSS_94") (pintype "power_in"))
    )
    (net (code "22") (name "Net-(C27-Pad1)") (class "Default")
      (node (ref "C27") (pin "1") (pinfunction "1_1") (pintype "passive"))
      (node (ref "R5") (pin "1") (pinfunction "1_1") (pintype "passive"))
      (node (ref "Y1") (pin "2") (pinfunction "2_2") (pintype "passive"))
    )
    (net (code "23") (name "Net-(D8-A)") (class "Default")
      (node (ref "D8") (pin "2") (pinfunction "A_2") (pintype "passive"))
      (node (ref "D9") (pin "1") (pinfunction "K_1") (pintype "passive"))
      (node (ref "R14") (pin "2") (pinfunction "2_2") (pintype "passive"))
      (node (ref "U3") (pin "4") (pinfunction "IN+_4") (pintype "input"))
    )
    (net (code "24") (name "Net-(R3-Pad1)") (class "Default")
      (node (ref "R3") (pin "1") (pinfunction "1_1") (pintype "passive"))
      (node (ref "SW1") (pin "2") (pinfunction "2_2") (pintype "passive"))
    )
    (net (code "25") (name "Net-(R7-Pad1)") (class "Default")
      (node (ref "R7") (pin "1") (pinfunction "1_1") (pintype "passive"))
      (node (ref "SW2") (pin "1") (pinfunction "1_1") (pintype "passive"))
    )
    (net (code "26") (name "Net-(R9-Pad1)") (class "Default")
      (node (ref "R9") (pin "1") (pinfunction "1_1") (pintype "passive"))
      (node (ref "SW2") (pin "2") (pinfunction "2_2") (pintype "passive"))
    )
    (net (code "27") (name "Net-(R11-Pad2)") (class "Default")
      (node (ref "R11") (pin "2") (pinfunction "2_2") (pintype "passive"))
      (node (ref "R12") (pin "1") (pinfunction "1_1") (pintype "passive"))
    )
    (net (code "28") (name "Net-(R13-Pad1)") (class "Default")
      (node (ref "R13") (pin "1") (pinfunction "1_1") (pintype "passive"))
      (node (ref "SW2") (pin "4") (pinfunction "4_4") (pintype "passive"))
    )
    (net (code "29") (name "Net-(SW2-C)") (class "Default")
      (node (ref "SW2") (pin "3") (pinfunction "C_3") (pintype "passive"))
      (node (ref "U3") (pin "2") (pinfunction "1_RG_2") (pintype "input"))
    )
    (net (code "30") (name "Net-(U2C-BOOT0)") (class "Default")
      (node (ref "R4") (pin "1") (pinfunction "1_1") (pintype "passive"))
      (node (ref "U2") (pin "138") (pinfunction "BOOT0_138") (pintype "output"))
    )
    (net (code "31") (name "Net-(U3-2_RG)") (class "Default")
      (node (ref "R13") (pin "2") (pinfunction "2_2") (pintype "passive"))
      (node (ref "R7") (pin "2") (pinfunction "2_2") (pintype "passive"))
      (node (ref "R9") (pin "2") (pinfunction "2_2") (pintype "passive"))
      (node (ref "U3") (pin "3") (pinfunction "2_RG_3") (pintype "input"))
    )
    (net (code "32") (name "Net-(U3-VOUT)") (class "Default")
      (node (ref "R8") (pin "1") (pinfunction "1_1") (pintype "passive"))
      (node (ref "U3") (pin "7") (pinfunction "VOUT_7") (pintype "output"))
    )
    (net (code "33") (name "Net-(U4A-IN+)") (class "Default")
      (node (ref "C31") (pin "1") (pinfunction "1_1") (pintype "passive"))
      (node (ref "R12") (pin "2") (pinfunction "2_2") (pintype "passive"))
      (node (ref "U4") (pin "3") (pinfunction "IN+_3") (pintype "input"))
    )
    (net (code "34") (name "Net-(U4A-IN-)") (class "Default")
      (node (ref "R10") (pin "1") (pinfunction "1_1") (pintype "passive"))
      (node (ref "U4") (pin "2") (pinfunction "IN-_2") (pintype "input"))
      (node (ref "U4") (pin "6") (pinfunction "OUT_6") (pintype "output"))
    )
    (net (code "35") (name "VBUS") (class "Default")
      (node (ref "C2") (pin "2") (pinfunction "A_2") (pintype "passive"))
      (node (ref "C3") (pin "1") (pinfunction "1_1") (pintype "passive"))
      (node (ref "J1") (pin "1") (pinfunction "VBUS_1") (pintype "power_in"))
      (node (ref "U1") (pin "3") (pinfunction "IN_3") (pintype "power_in"))
    )
    (net (code "36") (name "unconnected-(J1-ID-Pad4)") (class "Default")
      (node (ref "J1") (pin "4") (pinfunction "ID_4") (pintype "passive+no_connect"))
    )
    (net (code "37") (name "unconnected-(U2B-PB1-Pad47)") (class "Default")
      (node (ref "U2") (pin "47") (pinfunction "PB1_47") (pintype "bidirectional"))
    )
    (net (code "38") (name "unconnected-(U2B-PB2-Pad48)") (class "Default")
      (node (ref "U2") (pin "48") (pinfunction "PB2_48") (pintype "bidirectional"))
    )
    (net (code "39") (name "unconnected-(U2B-PB3-Pad133)") (class "Default")
      (node (ref "U2") (pin "133") (pinfunction "PB3_133") (pintype "bidirectional"))
    )
    (net (code "40") (name "unconnected-(U2B-PB4-Pad134)") (class "Default")
      (node (ref "U2") (pin "134") (pinfunction "PB4_134") (pintype "bidirectional"))
    )
    (net (code "41") (name "unconnected-(U2B-PB5-Pad135)") (class "Default")
      (node (ref "U2") (pin "135") (pinfunction "PB5_135") (pintype "bidirectional"))
    )
    (net (code "42") (name "unconnected-(U2B-PB6-Pad136)") (class "Default")
      (node (ref "U2") (pin "136") (pinfunction "PB6_136") (pintype "bidirectional"))
    )
    (net (code "43") (name "unconnected-(U2B-PB7-Pad137)") (class "Default")
      (node (ref "U2") (pin "137") (pinfunction "PB7_137") (pintype "bidirectional"))
    )
    (net (code "44") (name "unconnected-(U2B-PB8-Pad139)") (class "Default")
      (node (ref "U2") (pin "139") (pinfunction "PB8_139") (pintype "bidirectional"))
    )
    (net (code "45") (name "unconnected-(U2B-PB9-Pad140)") (class "Default")
      (node (ref "U2") (pin "140") (pinfunction "PB9_140") (pintype "bidirectional"))
    )
    (net (code "46") (name "unconnected-(U2B-PB10-Pad69)") (class "Default")
      (node (ref "U2") (pin "69") (pinfunction "PB10_69") (pintype "bidirectional"))
    )
    (net (code "47") (name "unconnected-(U2B-PB11-Pad70)") (class "Default")
      (node (ref "U2") (pin "70") (pinfunction "PB11_70") (pintype "bidirectional"))
    )
    (net (code "48") (name "unconnected-(U2B-PB12-Pad73)") (class "Default")
      (node (ref "U2") (pin "73") (pinfunction "PB12_73") (pintype "bidirectional"))
    )
    (net (code "49") (name "unconnected-(U2B-PB13-Pad74)") (class "Default")
      (node (ref "U2") (pin "74") (pinfunction "PB13_74") (pintype "bidirectional"))
    )
    (net (code "50") (name "unconnected-(U2B-PB14-Pad75)") (class "Default")
      (node (ref "U2") (pin "75") (pinfunction "PB14_75") (pintype "bidirectional"))
    )
    (net (code "51") (name "unconnected-(U2B-PB15-Pad76)") (class "Default")
      (node (ref "U2") (pin "76") (pinfunction "PB15_76") (pintype "bidirectional"))
    )
    (net (code "52") (name "unconnected-(U2B-PC0-Pad26)") (class "Default")
      (node (ref "U2") (pin "26") (pinfunction "PC0_26") (pintype "bidirectional"))
    )
    (net (code "53") (name "unconnected-(U2B-PC1-Pad27)") (class "Default")
      (node (ref "U2") (pin "27") (pinfunction "PC1_27") (pintype "bidirectional"))
    )
    (net (code "54") (name "unconnected-(U2B-PC2_C-Pad28)") (class "Default")
      (node (ref "U2") (pin "28") (pinfunction "PC2_C_28") (pintype "bidirectional"))
    )
    (net (code "55") (name "unconnected-(U2B-PC3_C-Pad29)") (class "Default")
      (node (ref "U2") (pin "29") (pinfunction "PC3_C_29") (pintype "bidirectional"))
    )
    (net (code "56") (name "unconnected-(U2B-PC4-Pad44)") (class "Default")
      (node (ref "U2") (pin "44") (pinfunction "PC4_44") (pintype "bidirectional"))
    )
    (net (code "57") (name "unconnected-(U2B-PC5-Pad45)") (class "Default")
      (node (ref "U2") (pin "45") (pinfunction "PC5_45") (pintype "bidirectional"))
    )
    (net (code "58") (name "unconnected-(U2B-PC6-Pad96)") (class "Default")
      (node (ref "U2") (pin "96") (pinfunction "PC6_96") (pintype "bidirectional"))
    )
    (net (code "59") (name "unconnected-(U2B-PC7-Pad97)") (class "Default")
      (node (ref "U2") (pin "97") (pinfunction "PC7_97") (pintype "bidirectional"))
    )
    (net (code "60") (name "unconnected-(U2B-PC8-Pad98)") (class "Default")
      (node (ref "U2") (pin "98") (pinfunction "PC8_98") (pintype "bidirectional"))
    )
    (net (code "61") (name "unconnected-(U2B-PC9-Pad99)") (class "Default")
      (node (ref "U2") (pin "99") (pinfunction "PC9_99") (pintype "bidirectional"))
    )
    (net (code "62") (name "unconnected-(U2B-PC10-Pad111)") (class "Default")
      (node (ref "U2") (pin "111") (pinfunction "PC10_111") (pintype "bidirectional"))
    )
    (net (code "63") (name "unconnected-(U2B-PC11-Pad112)") (class "Default")
      (node (ref "U2") (pin "112") (pinfunction "PC11_112") (pintype "bidirectional"))
    )
    (net (code "64") (name "unconnected-(U2B-PC12-Pad113)") (class "Default")
      (node (ref "U2") (pin "113") (pinfunction "PC12_113") (pintype "bidirectional"))
    )
    (net (code "65") (name "unconnected-(U2B-PC13-Pad7)") (class "Default")
      (node (ref "U2") (pin "7") (pinfunction "PC13_7") (pintype "bidirectional"))
    )
    (net (code "66") (name "unconnected-(U2B-PC14-OSC32_IN-Pad8)") (class "Default")
      (node (ref "U2") (pin "8") (pinfunction "PC14-OSC32_IN_8") (pintype "bidirectional"))
    )
    (net (code "67") (name "unconnected-(U2B-PC15-OSC32_OUT-Pad9)") (class "Default")
      (node (ref "U2") (pin "9") (pinfunction "PC15-OSC32_OUT_9") (pintype "bidirectional"))
    )
    (net (code "68") (name "unconnected-(U2B-PE0-Pad141)") (class "Default")
      (node (ref "U2") (pin "141") (pinfunction "PE0_141") (pintype "bidirectional"))
    )
    (net (code "69") (name "unconnected-(U2B-PE1-Pad142)") (class "Default")
      (node (ref "U2") (pin "142") (pinfunction "PE1_142") (pintype "bidirectional"))
    )
    (net (code "70") (name "unconnected-(U2B-PE2-Pad1)") (class "Default")
      (node (ref "U2") (pin "1") (pinfunction "PE2_1") (pintype "bidirectional"))
    )
    (net (code "71") (name "unconnected-(U2B-PE3-Pad2)") (class "Default")
      (node (ref "U2") (pin "2") (pinfunction "PE3_2") (pintype "bidirectional"))
    )
    (net (code "72") (name "unconnected-(U2B-PE4-Pad3)") (class "Default")
      (node (ref "U2") (pin "3") (pinfunction "PE4_3") (pintype "bidirectional"))
    )
    (net (code "73") (name "unconnected-(U2B-PE5-Pad4)") (class "Default")
      (node (ref "U2") (pin "4") (pinfunction "PE5_4") (pintype "bidirectional"))
    )
    (net (code "74") (name "unconnected-(U2B-PE6-Pad5)") (class "Default")
      (node (ref "U2") (pin "5") (pinfunction "PE6_5") (pintype "bidirectional"))
    )
    (net (code "75") (name "unconnected-(U2B-PE7-Pad58)") (class "Default")
      (node (ref "U2") (pin "58") (pinfunction "PE7_58") (pintype "bidirectional"))
    )
    (net (code "76") (name "unconnected-(U2B-PE8-Pad59)") (class "Default")
      (node (ref "U2") (pin "59") (pinfunction "PE8_59") (pintype "bidirectional"))
    )
    (net (code "77") (name "unconnected-(U2B-PE9-Pad60)") (class "Default")
      (node (ref "U2") (pin "60") (pinfunction "PE9_60") (pintype "bidirectional"))
    )
    (net (code "78") (name "unconnected-(U2B-PE10-Pad63)") (class "Default")
      (node (ref "U2") (pin "63") (pinfunction "PE10_63") (pintype "bidirectional"))
    )
    (net (code "79") (name "unconnected-(U2B-PE11-Pad64)") (class "Default")
      (node (ref "U2") (pin "64") (pinfunction "PE11_64") (pintype "bidirectional"))
    )
    (net (code "80") (name "unconnected-(U2B-PE12-Pad65)") (class "Default")
      (node (ref "U2") (pin "65") (pinfunction "PE12_65") (pintype "bidirectional"))
    )
    (net (code "81") (name "unconnected-(U2B-PE13-Pad66)") (class "Default")
      (node (ref "U2") (pin "66") (pinfunction "PE13_66") (pintype "bidirectional"))
    )
    (net (code "82") (name "unconnected-(U2B-PE14-Pad67)") (class "Default")
      (node (ref "U2") (pin "67") (pinfunction "PE14_67") (pintype "bidirectional"))
    )
    (net (code "83") (name "unconnected-(U2B-PE15-Pad68)") (class "Default")
      (node (ref "U2") (pin "68") (pinfunction "PE15_68") (pintype "bidirectional"))
    )
    (net (code "84") (name "unconnected-(U2B-PG0-Pad56)") (class "Default")
      (node (ref "U2") (pin "56") (pinfunction "PG0_56") (pintype "bidirectional"))
    )
    (net (code "85") (name "unconnected-(U2B-PG1-Pad57)") (class "Default")
      (node (ref "U2") (pin "57") (pinfunction "PG1_57") (pintype "bidirectional"))
    )
    (net (code "86") (name "unconnected-(U2B-PG2-Pad87)") (class "Default")
      (node (ref "U2") (pin "87") (pinfunction "PG2_87") (pintype "bidirectional"))
    )
    (net (code "87") (name "unconnected-(U2B-PG3-Pad88)") (class "Default")
      (node (ref "U2") (pin "88") (pinfunction "PG3_88") (pintype "bidirectional"))
    )
    (net (code "88") (name "unconnected-(U2B-PG4-Pad89)") (class "Default")
      (node (ref "U2") (pin "89") (pinfunction "PG4_89") (pintype "bidirectional"))
    )
    (net (code "89") (name "unconnected-(U2B-PG5-Pad90)") (class "Default")
      (node (ref "U2") (pin "90") (pinfunction "PG5_90") (pintype "bidirectional"))
    )
    (net (code "90") (name "unconnected-(U2B-PG6-Pad91)") (class "Default")
      (node (ref "U2") (pin "91") (pinfunction "PG6_91") (pintype "bidirectional"))
    )
    (net (code "91") (name "unconnected-(U2B-PG7-Pad92)") (class "Default")
      (node (ref "U2") (pin "92") (pinfunction "PG7_92") (pintype "bidirectional"))
    )
    (net (code "92") (name "unconnected-(U2B-PG8-Pad93)") (class "Default")
      (node (ref "U2") (pin "93") (pinfunction "PG8_93") (pintype "bidirectional"))
    )
    (net (code "93") (name "unconnected-(U2B-PG9-Pad124)") (class "Default")
      (node (ref "U2") (pin "124") (pinfunction "PG9_124") (pintype "bidirectional"))
    )
    (net (code "94") (name "unconnected-(U2B-PG10-Pad125)") (class "Default")
      (node (ref "U2") (pin "125") (pinfunction "PG10_125") (pintype "bidirectional"))
    )
    (net (code "95") (name "unconnected-(U2B-PG11-Pad126)") (class "Default")
      (node (ref "U2") (pin "126") (pinfunction "PG11_126") (pintype "bidirectional"))
    )
    (net (code "96") (name "unconnected-(U2B-PG12-Pad127)") (class "Default")
      (node (ref "U2") (pin "127") (pinfunction "PG12_127") (pintype "bidirectional"))
    )
    (net (code "97") (name "unconnected-(U2B-PG13-Pad128)") (class "Default")
      (node (ref "U2") (pin "128") (pinfunction "PG13_128") (pintype "bidirectional"))
    )
    (net (code "98") (name "unconnected-(U2B-PG14-Pad129)") (class "Default")
      (node (ref "U2") (pin "129") (pinfunction "PG14_129") (pintype "bidirectional"))
    )
    (net (code "99") (name "unconnected-(U2B-PG15-Pad132)") (class "Default")
      (node (ref "U2") (pin "132") (pinfunction "PG15_132") (pintype "bidirectional"))
    )
    (net (code "100") (name "unconnected-(U2C-PA2-Pad36)") (class "Default")
      (node (ref "U2") (pin "36") (pinfunction "PA2_36") (pintype "bidirectional"))
    )
    (net (code "101") (name "unconnected-(U2C-PA3-Pad37)") (class "Default")
      (node (ref "U2") (pin "37") (pinfunction "PA3_37") (pintype "bidirectional"))
    )
    (net (code "102") (name "unconnected-(U2C-PA4-Pad40)") (class "Default")
      (node (ref "U2") (pin "40") (pinfunction "PA4_40") (pintype "bidirectional"))
    )
    (net (code "103") (name "unconnected-(U2C-PA5-Pad41)") (class "Default")
      (node (ref "U2") (pin "41") (pinfunction "PA5_41") (pintype "bidirectional"))
    )
    (net (code "104") (name "unconnected-(U2C-PA6-Pad42)") (class "Default")
      (node (ref "U2") (pin "42") (pinfunction "PA6_42") (pintype "bidirectional"))
    )
    (net (code "105") (name "unconnected-(U2C-PA7-Pad43)") (class "Default")
      (node (ref "U2") (pin "43") (pinfunction "PA7_43") (pintype "bidirectional"))
    )
    (net (code "106") (name "unconnected-(U2C-PA8-Pad100)") (class "Default")
      (node (ref "U2") (pin "100") (pinfunction "PA8_100") (pintype "bidirectional"))
    )
    (net (code "107") (name "unconnected-(U2C-PA9-Pad101)") (class "Default")
      (node (ref "U2") (pin "101") (pinfunction "PA9_101") (pintype "bidirectional"))
    )
    (net (code "108") (name "unconnected-(U2C-PA10-Pad102)") (class "Default")
      (node (ref "U2") (pin "102") (pinfunction "PA10_102") (pintype "bidirectional"))
    )
    (net (code "109") (name "unconnected-(U2C-PA15-Pad110)") (class "Default")
      (node (ref "U2") (pin "110") (pinfunction "PA15_110") (pintype "bidirectional"))
    )
    (net (code "110") (name "unconnected-(U2C-PD0-Pad114)") (class "Default")
      (node (ref "U2") (pin "114") (pinfunction "PD0_114") (pintype "bidirectional"))
    )
    (net (code "111") (name "unconnected-(U2C-PD1-Pad115)") (class "Default")
      (node (ref "U2") (pin "115") (pinfunction "PD1_115") (pintype "bidirectional"))
    )
    (net (code "112") (name "unconnected-(U2C-PD2-Pad116)") (class "Default")
      (node (ref "U2") (pin "116") (pinfunction "PD2_116") (pintype "bidirectional"))
    )
    (net (code "113") (name "unconnected-(U2C-PD3-Pad117)") (class "Default")
      (node (ref "U2") (pin "117") (pinfunction "PD3_117") (pintype "bidirectional"))
    )
    (net (code "114") (name "unconnected-(U2C-PD4-Pad118)") (class "Default")
      (node (ref "U2") (pin "118") (pinfunction "PD4_118") (pintype "bidirectional"))
    )
    (net (code "115") (name "unconnected-(U2C-PD5-Pad119)") (class "Default")
      (node (ref "U2") (pin "119") (pinfunction "PD5_119") (pintype "bidirectional"))
    )
    (net (code "116") (name "unconnected-(U2C-PD6-Pad122)") (class "Default")
      (node (ref "U2") (pin "122") (pinfunction "PD6_122") (pintype "bidirectional"))
    )
    (net (code "117") (name "unconnected-(U2C-PD7-Pad123)") (class "Default")
      (node (ref "U2") (pin "123") (pinfunction "PD7_123") (pintype "bidirectional"))
    )
    (net (code "118") (name "unconnected-(U2C-PD8-Pad77)") (class "Default")
      (node (ref "U2") (pin "77") (pinfunction "PD8_77") (pintype "bidirectional"))
    )
    (net (code "119") (name "unconnected-(U2C-PD9-Pad78)") (class "Default")
      (node (ref "U2") (pin "78") (pinfunction "PD9_78") (pintype "bidirectional"))
    )
    (net (code "120") (name "unconnected-(U2C-PD10-Pad79)") (class "Default")
      (node (ref "U2") (pin "79") (pinfunction "PD10_79") (pintype "bidirectional"))
    )
    (net (code "121") (name "unconnected-(U2C-PD11-Pad80)") (class "Default")
      (node (ref "U2") (pin "80") (pinfunction "PD11_80") (pintype "bidirectional"))
    )
    (net (code "122") (name "unconnected-(U2C-PD12-Pad81)") (class "Default")
      (node (ref "U2") (pin "81") (pinfunction "PD12_81") (pintype "bidirectional"))
    )
    (net (code "123") (name "unconnected-(U2C-PD13-Pad82)") (class "Default")
      (node (ref "U2") (pin "82") (pinfunction "PD13_82") (pintype "bidirectional"))
    )
    (net (code "124") (name "unconnected-(U2C-PD14-Pad85)") (class "Default")
      (node (ref "U2") (pin "85") (pinfunction "PD14_85") (pintype "bidirectional"))
    )
    (net (code "125") (name "unconnected-(U2C-PD15-Pad86)") (class "Default")
      (node (ref "U2") (pin "86") (pinfunction "PD15_86") (pintype "bidirectional"))
    )
    (net (code "126") (name "unconnected-(U2C-PF0-Pad10)") (class "Default")
      (node (ref "U2") (pin "10") (pinfunction "PF0_10") (pintype "bidirectional"))
    )
    (net (code "127") (name "unconnected-(U2C-PF1-Pad11)") (class "Default")
      (node (ref "U2") (pin "11") (pinfunction "PF1_11") (pintype "bidirectional"))
    )
    (net (code "128") (name "unconnected-(U2C-PF2-Pad12)") (class "Default")
      (node (ref "U2") (pin "12") (pinfunction "PF2_12") (pintype "bidirectional"))
    )
    (net (code "129") (name "unconnected-(U2C-PF3-Pad13)") (class "Default")
      (node (ref "U2") (pin "13") (pinfunction "PF3_13") (pintype "bidirectional"))
    )
    (net (code "130") (name "unconnected-(U2C-PF4-Pad14)") (class "Default")
      (node (ref "U2") (pin "14") (pinfunction "PF4_14") (pintype "bidirectional"))
    )
    (net (code "131") (name "unconnected-(U2C-PF5-Pad15)") (class "Default")
      (node (ref "U2") (pin "15") (pinfunction "PF5_15") (pintype "bidirectional"))
    )
    (net (code "132") (name "unconnected-(U2C-PF6-Pad18)") (class "Default")
      (node (ref "U2") (pin "18") (pinfunction "PF6_18") (pintype "bidirectional"))
    )
    (net (code "133") (name "unconnected-(U2C-PF7-Pad19)") (class "Default")
      (node (ref "U2") (pin "19") (pinfunction "PF7_19") (pintype "bidirectional"))
    )
    (net (code "134") (name "unconnected-(U2C-PF8-Pad20)") (class "Default")
      (node (ref "U2") (pin "20") (pinfunction "PF8_20") (pintype "bidirectional"))
    )
    (net (code "135") (name "unconnected-(U2C-PF9-Pad21)") (class "Default")
      (node (ref "U2") (pin "21") (pinfunction "PF9_21") (pintype "bidirectional"))
    )
    (net (code "136") (name "unconnected-(U2C-PF10-Pad22)") (class "Default")
      (node (ref "U2") (pin "22") (pinfunction "PF10_22") (pintype "bidirectional"))
    )
    (net (code "137") (name "unconnected-(U2C-PF11-Pad49)") (class "Default")
      (node (ref "U2") (pin "49") (pinfunction "PF11_49") (pintype "bidirectional"))
    )
    (net (code "138") (name "unconnected-(U2C-PF12-Pad50)") (class "Default")
      (node (ref "U2") (pin "50") (pinfunction "PF12_50") (pintype "bidirectional"))
    )
    (net (code "139") (name "unconnected-(U2C-PF13-Pad53)") (class "Default")
      (node (ref "U2") (pin "53") (pinfunction "PF13_53") (pintype "bidirectional"))
    )
    (net (code "140") (name "unconnected-(U2C-PF14-Pad54)") (class "Default")
      (node (ref "U2") (pin "54") (pinfunction "PF14_54") (pintype "bidirectional"))
    )
    (net (code "141") (name "unconnected-(U2C-PF15-Pad55)") (class "Default")
      (node (ref "U2") (pin "55") (pinfunction "PF15_55") (pintype "bidirectional"))
    )
    (net (code "142") (name "unconnected-(U4B-NC-Pad1)") (class "Default")
      (node (ref "U4") (pin "1") (pinfunction "NC_1") (pintype "passive"))
    )
    (net (code "143") (name "unconnected-(U4B-NC-Pad5)") (class "Default")
      (node (ref "U4") (pin "5") (pinfunction "NC_5") (pintype "passive"))
    )
    (net (code "144") (name "unconnected-(U4B-NC-Pad8)") (class "Default")
      (node (ref "U4") (pin "8") (pinfunction "NC_8") (pintype "passive"))
    )
  )
)
